# PongSat_v3r6.net
KiCad netlist of a schematic drawn in EAGLE
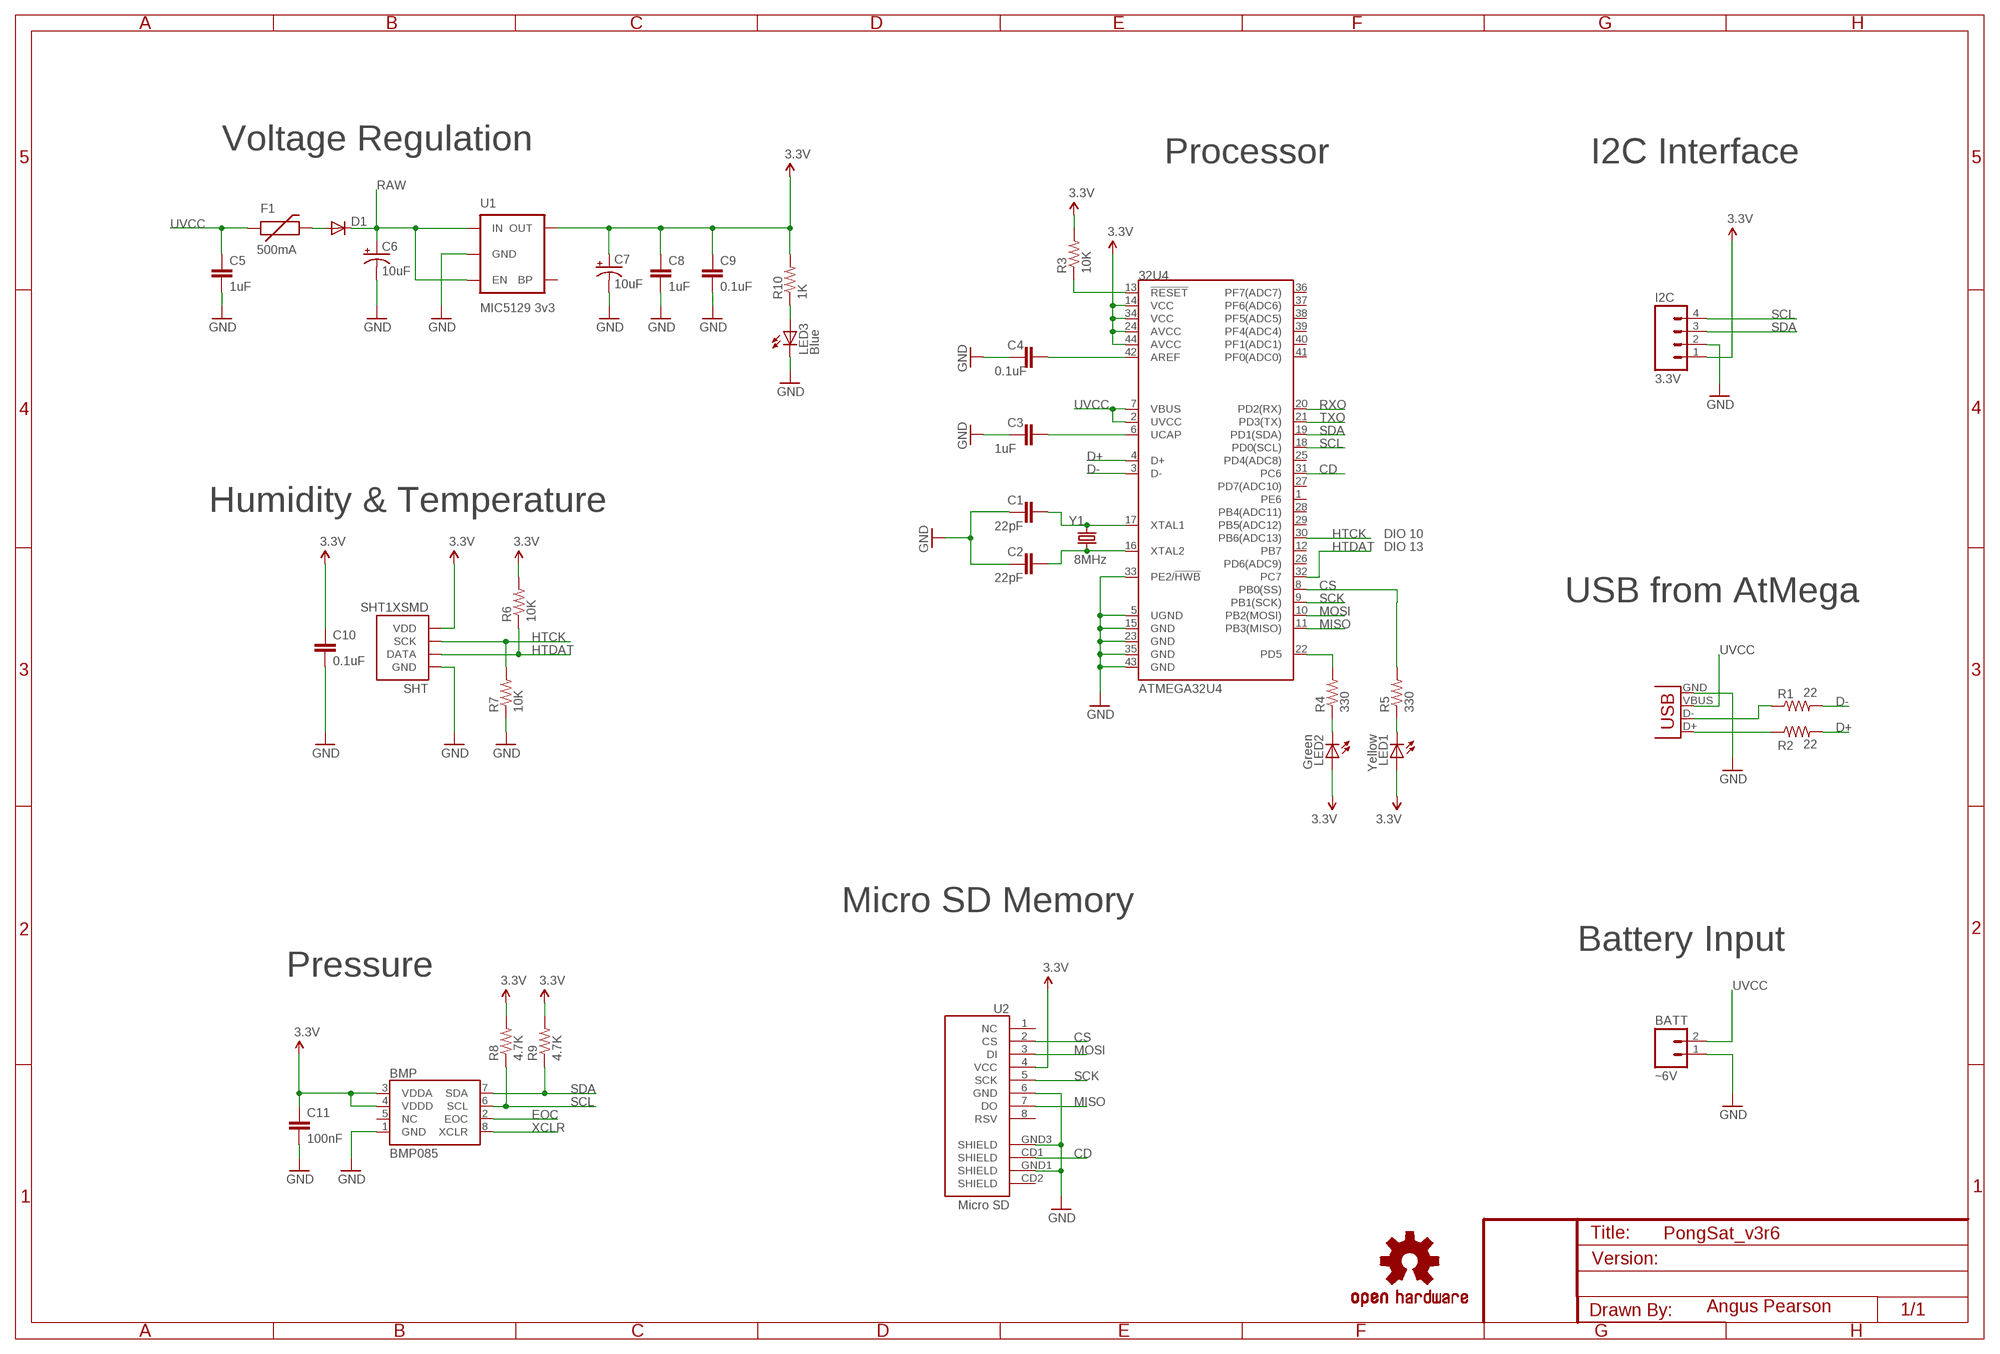
[diagram p0: schematic, sheet 1]

(export (version "E")
  (design (tool "Eeschema 10.0.6"))
  (components
    (comp (ref "32U4")
      (value "ATMEGA32U4")
      (footprint "eagle-import:QFN-44-NOPAD")
      (libsource (lib "eagle-import") (part "ATMEGA32U4QFN2"))
    )
    (comp (ref "BATT")
      (value "~6V")
      (footprint "eagle-import:1X02")
      (libsource (lib "eagle-import") (part "M02PTH"))
    )
    (comp (ref "BMP")
      (value "BMP085")
      (footprint "eagle-import:BMP085")
      (libsource (lib "eagle-import") (part "BMP085"))
    )
    (comp (ref "C1")
      (value "22pF")
      (footprint "eagle-import:0402-CAP")
      (libsource (lib "eagle-import") (part "CAP0402-CAP"))
    )
    (comp (ref "C2")
      (value "22pF")
      (footprint "eagle-import:0402-CAP")
      (libsource (lib "eagle-import") (part "CAP0402-CAP"))
    )
    (comp (ref "C3")
      (value "1uF")
      (footprint "eagle-import:0402-CAP")
      (libsource (lib "eagle-import") (part "CAP0402-CAP"))
    )
    (comp (ref "C4")
      (value "0.1uF")
      (footprint "eagle-import:0402-CAP")
      (libsource (lib "eagle-import") (part "CAP0402-CAP"))
    )
    (comp (ref "C5")
      (value "1uF")
      (footprint "eagle-import:0402-CAP")
      (libsource (lib "eagle-import") (part "CAP0402-CAP"))
    )
    (comp (ref "C6")
      (value "10uF")
      (footprint "eagle-import:EIA3216-KIT")
      (libsource (lib "eagle-import") (part "CAP_POL1206-KIT"))
    )
    (comp (ref "C7")
      (value "10uF")
      (footprint "eagle-import:EIA3216-KIT")
      (libsource (lib "eagle-import") (part "CAP_POL1206-KIT"))
    )
    (comp (ref "C8")
      (value "1uF")
      (footprint "eagle-import:0402-CAP")
      (libsource (lib "eagle-import") (part "CAP0402-CAP"))
    )
    (comp (ref "C9")
      (value "0.1uF")
      (footprint "eagle-import:0402-CAP")
      (libsource (lib "eagle-import") (part "CAP0402-CAP"))
    )
    (comp (ref "C10")
      (value "0.1uF")
      (footprint "eagle-import:0402-CAP")
      (libsource (lib "eagle-import") (part "CAP0402-CAP"))
    )
    (comp (ref "C11")
      (value "100nF")
      (footprint "eagle-import:0402-CAP")
      (libsource (lib "eagle-import") (part "CAP0402-CAP"))
    )
    (comp (ref "D1")
      (value "DIODESOT23")
      (footprint "eagle-import:SOT23-3")
      (libsource (lib "eagle-import") (part "DIODESOT23"))
    )
    (comp (ref "F1")
      (value "500mA")
      (footprint "eagle-import:0603")
      (libsource (lib "eagle-import") (part "PTC0603"))
    )
    (comp (ref "I2C")
      (value "3.3V")
      (footprint "eagle-import:1X04")
      (libsource (lib "eagle-import") (part "M04PTH"))
    )
    (comp (ref "LED1")
      (value "Yellow")
      (footprint "eagle-import:LED-0603")
      (libsource (lib "eagle-import") (part "LED0603"))
    )
    (comp (ref "LED2")
      (value "Green")
      (footprint "eagle-import:LED-0603")
      (libsource (lib "eagle-import") (part "LED0603"))
    )
    (comp (ref "LED3")
      (value "Blue")
      (footprint "eagle-import:LED-0603")
      (libsource (lib "eagle-import") (part "LED0603"))
    )
    (comp (ref "R1")
      (value "22")
      (footprint "eagle-import:0402-RES")
      (libsource (lib "eagle-import") (part "RESISTOR0402-RES"))
    )
    (comp (ref "R2")
      (value "22")
      (footprint "eagle-import:0402-RES")
      (libsource (lib "eagle-import") (part "RESISTOR0402-RES"))
    )
    (comp (ref "R3")
      (value "10K")
      (footprint "eagle-import:0402-RES")
      (libsource (lib "eagle-import") (part "RESISTOR0402-RES"))
    )
    (comp (ref "R4")
      (value "330")
      (footprint "eagle-import:0402-RES")
      (libsource (lib "eagle-import") (part "RESISTOR0402-RES"))
    )
    (comp (ref "R5")
      (value "330")
      (footprint "eagle-import:0402-RES")
      (libsource (lib "eagle-import") (part "RESISTOR0402-RES"))
    )
    (comp (ref "R6")
      (value "10K")
      (footprint "eagle-import:0402-RES")
      (libsource (lib "eagle-import") (part "RESISTOR0402-RES"))
    )
    (comp (ref "R7")
      (value "10K")
      (footprint "eagle-import:0402-RES")
      (libsource (lib "eagle-import") (part "RESISTOR0402-RES"))
    )
    (comp (ref "R8")
      (value "4.7K")
      (footprint "eagle-import:0402-RES")
      (libsource (lib "eagle-import") (part "RESISTOR0402-RES"))
    )
    (comp (ref "R9")
      (value "4.7K")
      (footprint "eagle-import:0402-RES")
      (libsource (lib "eagle-import") (part "RESISTOR0402-RES"))
    )
    (comp (ref "R10")
      (value "1K")
      (footprint "eagle-import:0402-RES")
      (libsource (lib "eagle-import") (part "RESISTOR0402-RES"))
    )
    (comp (ref "SHT")
      (value "SHT1XSMD")
      (footprint "eagle-import:SHT1X")
      (libsource (lib "eagle-import") (part "SHT1XSMD"))
    )
    (comp (ref "U$2")
      (value "OSHW-LOGOS")
      (footprint "eagle-import:OSHW-LOGO-S")
      (libsource (lib "eagle-import") (part "OSHW-LOGOS"))
    )
    (comp (ref "U1")
      (value "MIC5129 3v3")
      (footprint "eagle-import:SOT23-5")
      (libsource (lib "eagle-import") (part "V_REG_MIC5219SMD"))
    )
    (comp (ref "U2")
      (value "Micro SD")
      (footprint "eagle-import:MICRO-SD-SOCKET-PP")
      (libsource (lib "eagle-import") (part "USD-SOCKETNEW"))
    )
    (comp (ref "X1")
      (value "USB-MICROB")
      (footprint "eagle-import:USB-MICROB")
      (libsource (lib "eagle-import") (part "USB-MICROB"))
    )
    (comp (ref "Y1")
      (value "8MHz")
      (footprint "eagle-import:CRYSTAL-SMD-5X3")
      (libsource (lib "eagle-import") (part "CRYSTAL5X3"))
    )
  )
  (nets
    (net (code "1") (name "/CD") (class "Default")
      (node (ref "32U4") (pin "31") (pinfunction "PC6_31") (pintype "bidirectional"))
      (node (ref "U2") (pin "CD1") (pinfunction "SHIELD_CD1") (pintype "bidirectional"))
    )
    (net (code "2") (name "/CS") (class "Default")
      (node (ref "32U4") (pin "8") (pinfunction "PB0(SS)_8") (pintype "bidirectional"))
      (node (ref "R5") (pin "2") (pinfunction "2_2") (pintype "passive"))
      (node (ref "U2") (pin "2") (pinfunction "CS_2") (pintype "bidirectional"))
    )
    (net (code "3") (name "/D+") (class "Default")
      (node (ref "32U4") (pin "4") (pinfunction "D+_4") (pintype "bidirectional"))
      (node (ref "R2") (pin "2") (pinfunction "2_2") (pintype "passive"))
    )
    (net (code "4") (name "/D-") (class "Default")
      (node (ref "32U4") (pin "3") (pinfunction "D-_3") (pintype "bidirectional"))
      (node (ref "R1") (pin "2") (pinfunction "2_2") (pintype "passive"))
    )
    (net (code "5") (name "/EOC") (class "Default")
      (node (ref "BMP") (pin "2") (pinfunction "EOC_2") (pintype "output"))
    )
    (net (code "6") (name "/HTCK") (class "Default")
      (node (ref "32U4") (pin "30") (pinfunction "PB6(ADC13)_30") (pintype "bidirectional"))
      (node (ref "R7") (pin "2") (pinfunction "2_2") (pintype "passive"))
      (node (ref "SHT") (pin "3") (pinfunction "SCK_3") (pintype "input"))
    )
    (net (code "7") (name "/HTDAT") (class "Default")
      (node (ref "32U4") (pin "32") (pinfunction "PC7_32") (pintype "bidirectional"))
      (node (ref "R6") (pin "1") (pinfunction "1_1") (pintype "passive"))
      (node (ref "SHT") (pin "2") (pinfunction "DATA_2") (pintype "bidirectional"))
    )
    (net (code "8") (name "/MISO") (class "Default")
      (node (ref "32U4") (pin "11") (pinfunction "PB3(MISO)_11") (pintype "bidirectional"))
      (node (ref "U2") (pin "7") (pinfunction "DO_7") (pintype "bidirectional"))
    )
    (net (code "9") (name "/MOSI") (class "Default")
      (node (ref "32U4") (pin "10") (pinfunction "PB2(MOSI)_10") (pintype "bidirectional"))
      (node (ref "U2") (pin "3") (pinfunction "DI_3") (pintype "bidirectional"))
    )
    (net (code "10") (name "/RAW") (class "Default")
      (node (ref "C6") (pin "A") (pinfunction "+_A") (pintype "passive"))
      (node (ref "D1") (pin "3") (pinfunction "C_3") (pintype "passive"))
      (node (ref "U1") (pin "1") (pinfunction "IN_1") (pintype "input"))
      (node (ref "U1") (pin "3") (pinfunction "EN_3") (pintype "input"))
    )
    (net (code "11") (name "/RXO") (class "Default")
      (node (ref "32U4") (pin "20") (pinfunction "PD2(RX)_20") (pintype "bidirectional"))
    )
    (net (code "12") (name "/SCK") (class "Default")
      (node (ref "32U4") (pin "9") (pinfunction "PB1(SCK)_9") (pintype "bidirectional"))
      (node (ref "U2") (pin "5") (pinfunction "SCK_5") (pintype "bidirectional"))
    )
    (net (code "13") (name "/SCL") (class "Default")
      (node (ref "32U4") (pin "18") (pinfunction "PD0(SCL)_18") (pintype "bidirectional"))
      (node (ref "BMP") (pin "6") (pinfunction "SCL_6") (pintype "input"))
      (node (ref "I2C") (pin "4") (pinfunction "4_4") (pintype "passive"))
      (node (ref "R8") (pin "1") (pinfunction "1_1") (pintype "passive"))
    )
    (net (code "14") (name "/SDA") (class "Default")
      (node (ref "32U4") (pin "19") (pinfunction "PD1(SDA)_19") (pintype "bidirectional"))
      (node (ref "BMP") (pin "7") (pinfunction "SDA_7") (pintype "bidirectional"))
      (node (ref "I2C") (pin "3") (pinfunction "3_3") (pintype "passive"))
      (node (ref "R9") (pin "1") (pinfunction "1_1") (pintype "passive"))
    )
    (net (code "15") (name "/TXO") (class "Default")
      (node (ref "32U4") (pin "21") (pinfunction "PD3(TX)_21") (pintype "bidirectional"))
    )
    (net (code "16") (name "/UVCC") (class "Default")
      (node (ref "32U4") (pin "2") (pinfunction "UVCC_2") (pintype "bidirectional"))
      (node (ref "32U4") (pin "7") (pinfunction "VBUS_7") (pintype "bidirectional"))
      (node (ref "BATT") (pin "2") (pinfunction "2_2") (pintype "passive"))
      (node (ref "C5") (pin "1") (pinfunction "1_1") (pintype "passive"))
      (node (ref "F1") (pin "1") (pinfunction "1_1") (pintype "bidirectional"))
      (node (ref "X1") (pin "VBUS") (pinfunction "VBUS_VBUS") (pintype "bidirectional"))
    )
    (net (code "17") (name "/XCLR") (class "Default")
      (node (ref "BMP") (pin "8") (pinfunction "XCLR_8") (pintype "input"))
    )
    (net (code "18") (name "3.3V") (class "Default")
      (node (ref "32U4") (pin "14") (pinfunction "VCC_14") (pintype "bidirectional"))
      (node (ref "32U4") (pin "24") (pinfunction "AVCC_24") (pintype "bidirectional"))
      (node (ref "32U4") (pin "34") (pinfunction "VCC_34") (pintype "bidirectional"))
      (node (ref "32U4") (pin "44") (pinfunction "AVCC_44") (pintype "bidirectional"))
      (node (ref "BMP") (pin "3") (pinfunction "VDDA_3") (pintype "power_in"))
      (node (ref "BMP") (pin "4") (pinfunction "VDDD_4") (pintype "power_in"))
      (node (ref "C10") (pin "1") (pinfunction "1_1") (pintype "passive"))
      (node (ref "C11") (pin "1") (pinfunction "1_1") (pintype "passive"))
      (node (ref "C7") (pin "A") (pinfunction "+_A") (pintype "passive"))
      (node (ref "C8") (pin "1") (pinfunction "1_1") (pintype "passive"))
      (node (ref "C9") (pin "1") (pinfunction "1_1") (pintype "passive"))
      (node (ref "I2C") (pin "1") (pinfunction "1_1") (pintype "passive"))
      (node (ref "LED1") (pin "A") (pinfunction "A_A") (pintype "passive"))
      (node (ref "LED2") (pin "A") (pinfunction "A_A") (pintype "passive"))
      (node (ref "R10") (pin "2") (pinfunction "2_2") (pintype "passive"))
      (node (ref "R3") (pin "2") (pinfunction "2_2") (pintype "passive"))
      (node (ref "R6") (pin "2") (pinfunction "2_2") (pintype "passive"))
      (node (ref "R8") (pin "2") (pinfunction "2_2") (pintype "passive"))
      (node (ref "R9") (pin "2") (pinfunction "2_2") (pintype "passive"))
      (node (ref "SHT") (pin "4") (pinfunction "VDD_4") (pintype "power_in"))
      (node (ref "U1") (pin "5") (pinfunction "OUT_5") (pintype "passive"))
      (node (ref "U2") (pin "4") (pinfunction "VCC_4") (pintype "bidirectional"))
    )
    (net (code "19") (name "GND") (class "Default")
      (node (ref "32U4") (pin "15") (pinfunction "GND_15") (pintype "bidirectional"))
      (node (ref "32U4") (pin "23") (pinfunction "GND_23") (pintype "bidirectional"))
      (node (ref "32U4") (pin "33") (pinfunction "PE2/~{HWB}_33") (pintype "bidirectional"))
      (node (ref "32U4") (pin "35") (pinfunction "GND_35") (pintype "bidirectional"))
      (node (ref "32U4") (pin "43") (pinfunction "GND_43") (pintype "bidirectional"))
      (node (ref "32U4") (pin "5") (pinfunction "UGND_5") (pintype "bidirectional"))
      (node (ref "BATT") (pin "1") (pinfunction "1_1") (pintype "passive"))
      (node (ref "BMP") (pin "1") (pinfunction "GND_1") (pintype "power_in"))
      (node (ref "C1") (pin "1") (pinfunction "1_1") (pintype "passive"))
      (node (ref "C10") (pin "2") (pinfunction "2_2") (pintype "passive"))
      (node (ref "C11") (pin "2") (pinfunction "2_2") (pintype "passive"))
      (node (ref "C2") (pin "1") (pinfunction "1_1") (pintype "passive"))
      (node (ref "C3") (pin "1") (pinfunction "1_1") (pintype "passive"))
      (node (ref "C4") (pin "1") (pinfunction "1_1") (pintype "passive"))
      (node (ref "C5") (pin "2") (pinfunction "2_2") (pintype "passive"))
      (node (ref "C6") (pin "C") (pinfunction "-_C") (pintype "passive"))
      (node (ref "C7") (pin "C") (pinfunction "-_C") (pintype "passive"))
      (node (ref "C8") (pin "2") (pinfunction "2_2") (pintype "passive"))
      (node (ref "C9") (pin "2") (pinfunction "2_2") (pintype "passive"))
      (node (ref "I2C") (pin "2") (pinfunction "2_2") (pintype "passive"))
      (node (ref "LED3") (pin "C") (pinfunction "C_C") (pintype "passive"))
      (node (ref "R7") (pin "1") (pinfunction "1_1") (pintype "passive"))
      (node (ref "SHT") (pin "1") (pinfunction "GND_1") (pintype "power_in"))
      (node (ref "U1") (pin "2") (pinfunction "GND_2") (pintype "input"))
      (node (ref "U2") (pin "6") (pinfunction "GND_6") (pintype "bidirectional"))
      (node (ref "U2") (pin "GND1") (pinfunction "SHIELD_GND1") (pintype "bidirectional"))
      (node (ref "U2") (pin "GND3") (pinfunction "SHIELD_GND3") (pintype "bidirectional"))
      (node (ref "X1") (pin "GND") (pinfunction "GND_GND") (pintype "bidirectional"))
    )
    (net (code "20") (name "Net-(32U4-AREF)") (class "Default")
      (node (ref "32U4") (pin "42") (pinfunction "AREF_42") (pintype "bidirectional"))
      (node (ref "C4") (pin "2") (pinfunction "2_2") (pintype "passive"))
    )
    (net (code "21") (name "Net-(32U4-PD5)") (class "Default")
      (node (ref "32U4") (pin "22") (pinfunction "PD5_22") (pintype "bidirectional"))
      (node (ref "R4") (pin "2") (pinfunction "2_2") (pintype "passive"))
    )
    (net (code "22") (name "Net-(32U4-UCAP)") (class "Default")
      (node (ref "32U4") (pin "6") (pinfunction "UCAP_6") (pintype "bidirectional"))
      (node (ref "C3") (pin "2") (pinfunction "2_2") (pintype "passive"))
    )
    (net (code "23") (name "Net-(32U4-XTAL1)") (class "Default")
      (node (ref "32U4") (pin "17") (pinfunction "XTAL1_17") (pintype "bidirectional"))
      (node (ref "C1") (pin "2") (pinfunction "2_2") (pintype "passive"))
      (node (ref "Y1") (pin "3") (pinfunction "2_3") (pintype "passive"))
    )
    (net (code "24") (name "Net-(32U4-XTAL2)") (class "Default")
      (node (ref "32U4") (pin "16") (pinfunction "XTAL2_16") (pintype "bidirectional"))
      (node (ref "C2") (pin "2") (pinfunction "2_2") (pintype "passive"))
      (node (ref "Y1") (pin "1") (pinfunction "1_1") (pintype "passive"))
    )
    (net (code "25") (name "Net-(32U4-~{RESET})") (class "Default")
      (node (ref "32U4") (pin "13") (pinfunction "~{RESET}_13") (pintype "bidirectional"))
      (node (ref "R3") (pin "1") (pinfunction "1_1") (pintype "passive"))
    )
    (net (code "26") (name "Net-(D1-A)") (class "Default")
      (node (ref "D1") (pin "1") (pinfunction "A_1") (pintype "passive"))
      (node (ref "F1") (pin "2") (pinfunction "2_2") (pintype "bidirectional"))
    )
    (net (code "27") (name "Net-(LED1-PadC)") (class "Default")
      (node (ref "LED1") (pin "C") (pinfunction "C_C") (pintype "passive"))
      (node (ref "R5") (pin "1") (pinfunction "1_1") (pintype "passive"))
    )
    (net (code "28") (name "Net-(LED2-PadC)") (class "Default")
      (node (ref "LED2") (pin "C") (pinfunction "C_C") (pintype "passive"))
      (node (ref "R4") (pin "1") (pinfunction "1_1") (pintype "passive"))
    )
    (net (code "29") (name "Net-(LED3-PadA)") (class "Default")
      (node (ref "LED3") (pin "A") (pinfunction "A_A") (pintype "passive"))
      (node (ref "R10") (pin "1") (pinfunction "1_1") (pintype "passive"))
    )
    (net (code "30") (name "Net-(R1-Pad1)") (class "Default")
      (node (ref "R1") (pin "1") (pinfunction "1_1") (pintype "passive"))
      (node (ref "X1") (pin "D-") (pinfunction "D-_D-") (pintype "bidirectional"))
    )
    (net (code "31") (name "Net-(R2-Pad1)") (class "Default")
      (node (ref "R2") (pin "1") (pinfunction "1_1") (pintype "passive"))
      (node (ref "X1") (pin "D+") (pinfunction "D+_D+") (pintype "bidirectional"))
    )
    (net (code "32") (name "unconnected-(32U4-PB4(ADC11)-Pad28)") (class "Default")
      (node (ref "32U4") (pin "28") (pinfunction "PB4(ADC11)_28") (pintype "bidirectional"))
    )
    (net (code "33") (name "unconnected-(32U4-PB5(ADC12)-Pad29)") (class "Default")
      (node (ref "32U4") (pin "29") (pinfunction "PB5(ADC12)_29") (pintype "bidirectional"))
    )
    (net (code "34") (name "unconnected-(32U4-PB7-Pad12)") (class "Default")
      (node (ref "32U4") (pin "12") (pinfunction "PB7_12") (pintype "bidirectional"))
    )
    (net (code "35") (name "unconnected-(32U4-PD4(ADC8)-Pad25)") (class "Default")
      (node (ref "32U4") (pin "25") (pinfunction "PD4(ADC8)_25") (pintype "bidirectional"))
    )
    (net (code "36") (name "unconnected-(32U4-PD6(ADC9)-Pad26)") (class "Default")
      (node (ref "32U4") (pin "26") (pinfunction "PD6(ADC9)_26") (pintype "bidirectional"))
    )
    (net (code "37") (name "unconnected-(32U4-PD7(ADC10)-Pad27)") (class "Default")
      (node (ref "32U4") (pin "27") (pinfunction "PD7(ADC10)_27") (pintype "bidirectional"))
    )
    (net (code "38") (name "unconnected-(32U4-PE6-Pad1)") (class "Default")
      (node (ref "32U4") (pin "1") (pinfunction "PE6_1") (pintype "bidirectional"))
    )
    (net (code "39") (name "unconnected-(32U4-PF0(ADC0)-Pad41)") (class "Default")
      (node (ref "32U4") (pin "41") (pinfunction "PF0(ADC0)_41") (pintype "bidirectional"))
    )
    (net (code "40") (name "unconnected-(32U4-PF1(ADC1)-Pad40)") (class "Default")
      (node (ref "32U4") (pin "40") (pinfunction "PF1(ADC1)_40") (pintype "bidirectional"))
    )
    (net (code "41") (name "unconnected-(32U4-PF4(ADC4)-Pad39)") (class "Default")
      (node (ref "32U4") (pin "39") (pinfunction "PF4(ADC4)_39") (pintype "bidirectional"))
    )
    (net (code "42") (name "unconnected-(32U4-PF5(ADC5)-Pad38)") (class "Default")
      (node (ref "32U4") (pin "38") (pinfunction "PF5(ADC5)_38") (pintype "bidirectional"))
    )
    (net (code "43") (name "unconnected-(32U4-PF6(ADC6)-Pad37)") (class "Default")
      (node (ref "32U4") (pin "37") (pinfunction "PF6(ADC6)_37") (pintype "bidirectional"))
    )
    (net (code "44") (name "unconnected-(32U4-PF7(ADC7)-Pad36)") (class "Default")
      (node (ref "32U4") (pin "36") (pinfunction "PF7(ADC7)_36") (pintype "bidirectional"))
    )
    (net (code "45") (name "unconnected-(BMP-NC-Pad5)") (class "Default")
      (node (ref "BMP") (pin "5") (pinfunction "NC_5") (pintype "bidirectional"))
    )
    (net (code "46") (name "unconnected-(U1-BP-Pad4)") (class "Default")
      (node (ref "U1") (pin "4") (pinfunction "BP_4") (pintype "input"))
    )
    (net (code "47") (name "unconnected-(U2-NC-Pad1)") (class "Default")
      (node (ref "U2") (pin "1") (pinfunction "NC_1") (pintype "bidirectional"))
    )
    (net (code "48") (name "unconnected-(U2-RSV-Pad8)") (class "Default")
      (node (ref "U2") (pin "8") (pinfunction "RSV_8") (pintype "bidirectional"))
    )
    (net (code "49") (name "unconnected-(U2-SHIELD-PadCD2)") (class "Default")
      (node (ref "U2") (pin "CD2") (pinfunction "SHIELD_CD2") (pintype "bidirectional"))
    )
  )
)
